# Driver.net
KiCad netlist of a schematic drawn in Altium Designer
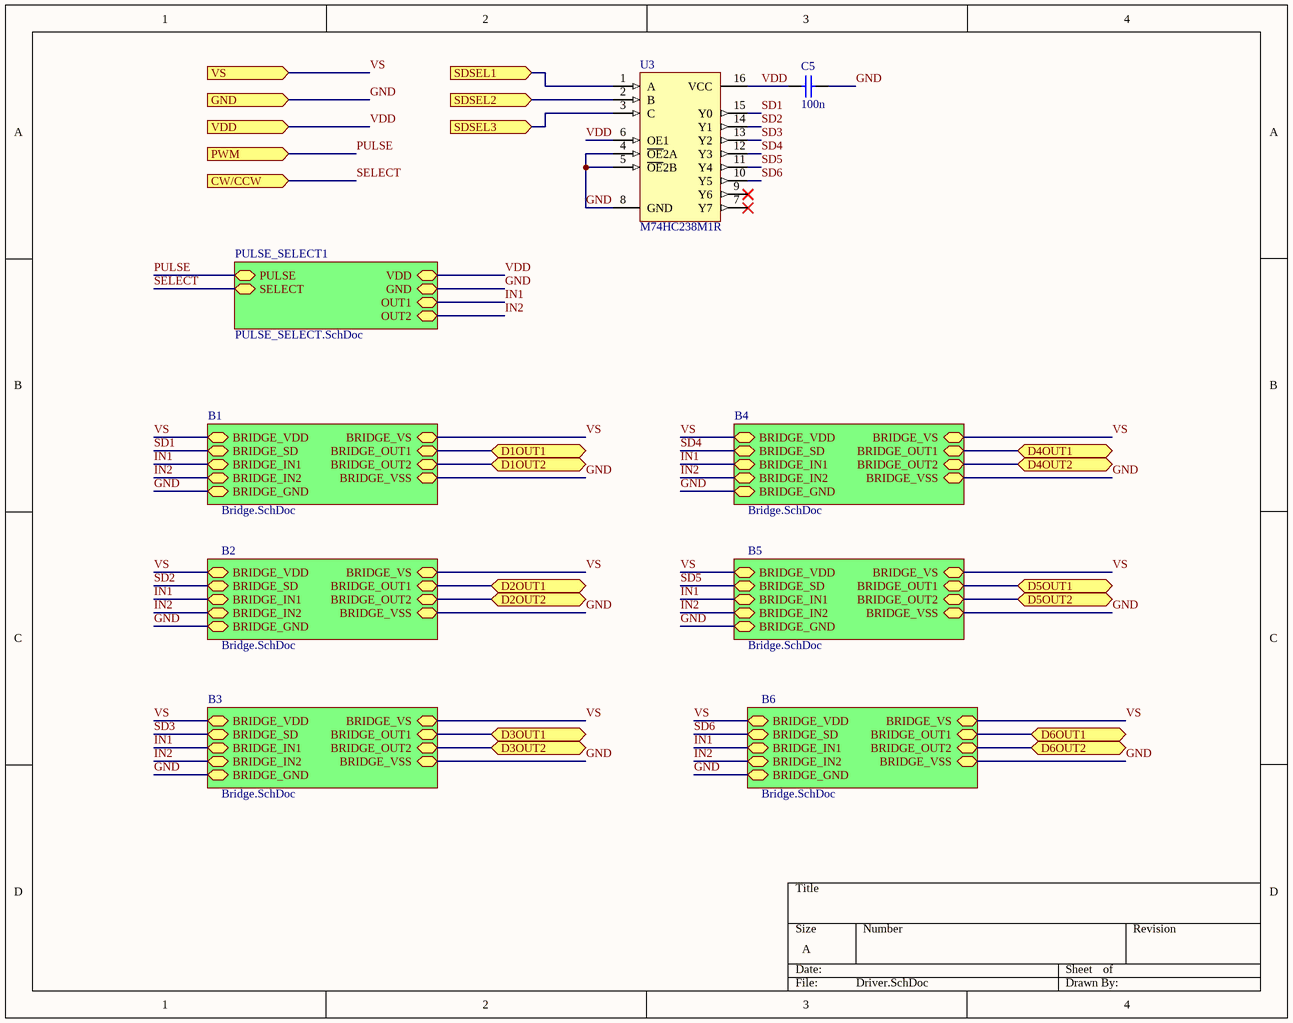
[diagram p0: Driver.SchDoc]

(export (version "E")
  (design (tool "Eeschema 10.0.6"))
  (components
    (comp (ref "C5")
      (value "100n")
      (footprint "MY_CAP_SMD_0805")
      (libsource (lib "AMINLIB") (part "CAP SMD"))
    )
    (comp (ref "U3")
      (value "M74HC238M1R")
      (footprint "SO16_N")
      (description "3-to-8 Line Decoder")
      (fields (field (name "PUBLISHER") "Altium Limited"))
      (libsource (lib "ST Logic Decoder") (part "M74HC238M1R"))
    )
  )
  (nets
    (net (code "13") (name "/GND") (class "Default")
      (node (ref "C5") (pin "1") (pinfunction "1_1") (pintype "passive"))
      (node (ref "U3") (pin "4") (pinfunction "~{OE}2A_4") (pintype "input"))
      (node (ref "U3") (pin "5") (pinfunction "~{OE}2B_5") (pintype "input"))
      (node (ref "U3") (pin "8") (pinfunction "GND_8") (pintype "passive"))
    )
    (net (code "17") (name "/SD1") (class "Default")
      (node (ref "U3") (pin "15") (pinfunction "Y0_15") (pintype "output"))
    )
    (net (code "18") (name "/SD2") (class "Default")
      (node (ref "U3") (pin "14") (pinfunction "Y1_14") (pintype "output"))
    )
    (net (code "19") (name "/SD3") (class "Default")
      (node (ref "U3") (pin "13") (pinfunction "Y2_13") (pintype "output"))
    )
    (net (code "20") (name "/SD4") (class "Default")
      (node (ref "U3") (pin "12") (pinfunction "Y3_12") (pintype "output"))
    )
    (net (code "21") (name "/SD5") (class "Default")
      (node (ref "U3") (pin "11") (pinfunction "Y4_11") (pintype "output"))
    )
    (net (code "22") (name "/SD6") (class "Default")
      (node (ref "U3") (pin "10") (pinfunction "Y5_10") (pintype "output"))
    )
    (net (code "23") (name "/SDSEL1") (class "Default")
      (node (ref "U3") (pin "1") (pinfunction "A_1") (pintype "input"))
    )
    (net (code "24") (name "/SDSEL2") (class "Default")
      (node (ref "U3") (pin "2") (pinfunction "B_2") (pintype "input"))
    )
    (net (code "25") (name "/SDSEL3") (class "Default")
      (node (ref "U3") (pin "3") (pinfunction "C_3") (pintype "input"))
    )
    (net (code "27") (name "/VDD") (class "Default")
      (node (ref "C5") (pin "2") (pinfunction "2_2") (pintype "passive"))
      (node (ref "U3") (pin "16") (pinfunction "VCC_16") (pintype "passive"))
      (node (ref "U3") (pin "6") (pinfunction "OE1_6") (pintype "input"))
    )
    (net (code "29") (name "unconnected-(U3-Y6-Pad9)") (class "Default")
      (node (ref "U3") (pin "9") (pinfunction "Y6_9") (pintype "output+no_connect"))
    )
    (net (code "30") (name "unconnected-(U3-Y7-Pad7)") (class "Default")
      (node (ref "U3") (pin "7") (pinfunction "Y7_7") (pintype "output+no_connect"))
    )
  )
)
